# openbook_schematic.net
KiCad netlist of a schematic drawn in EAGLE
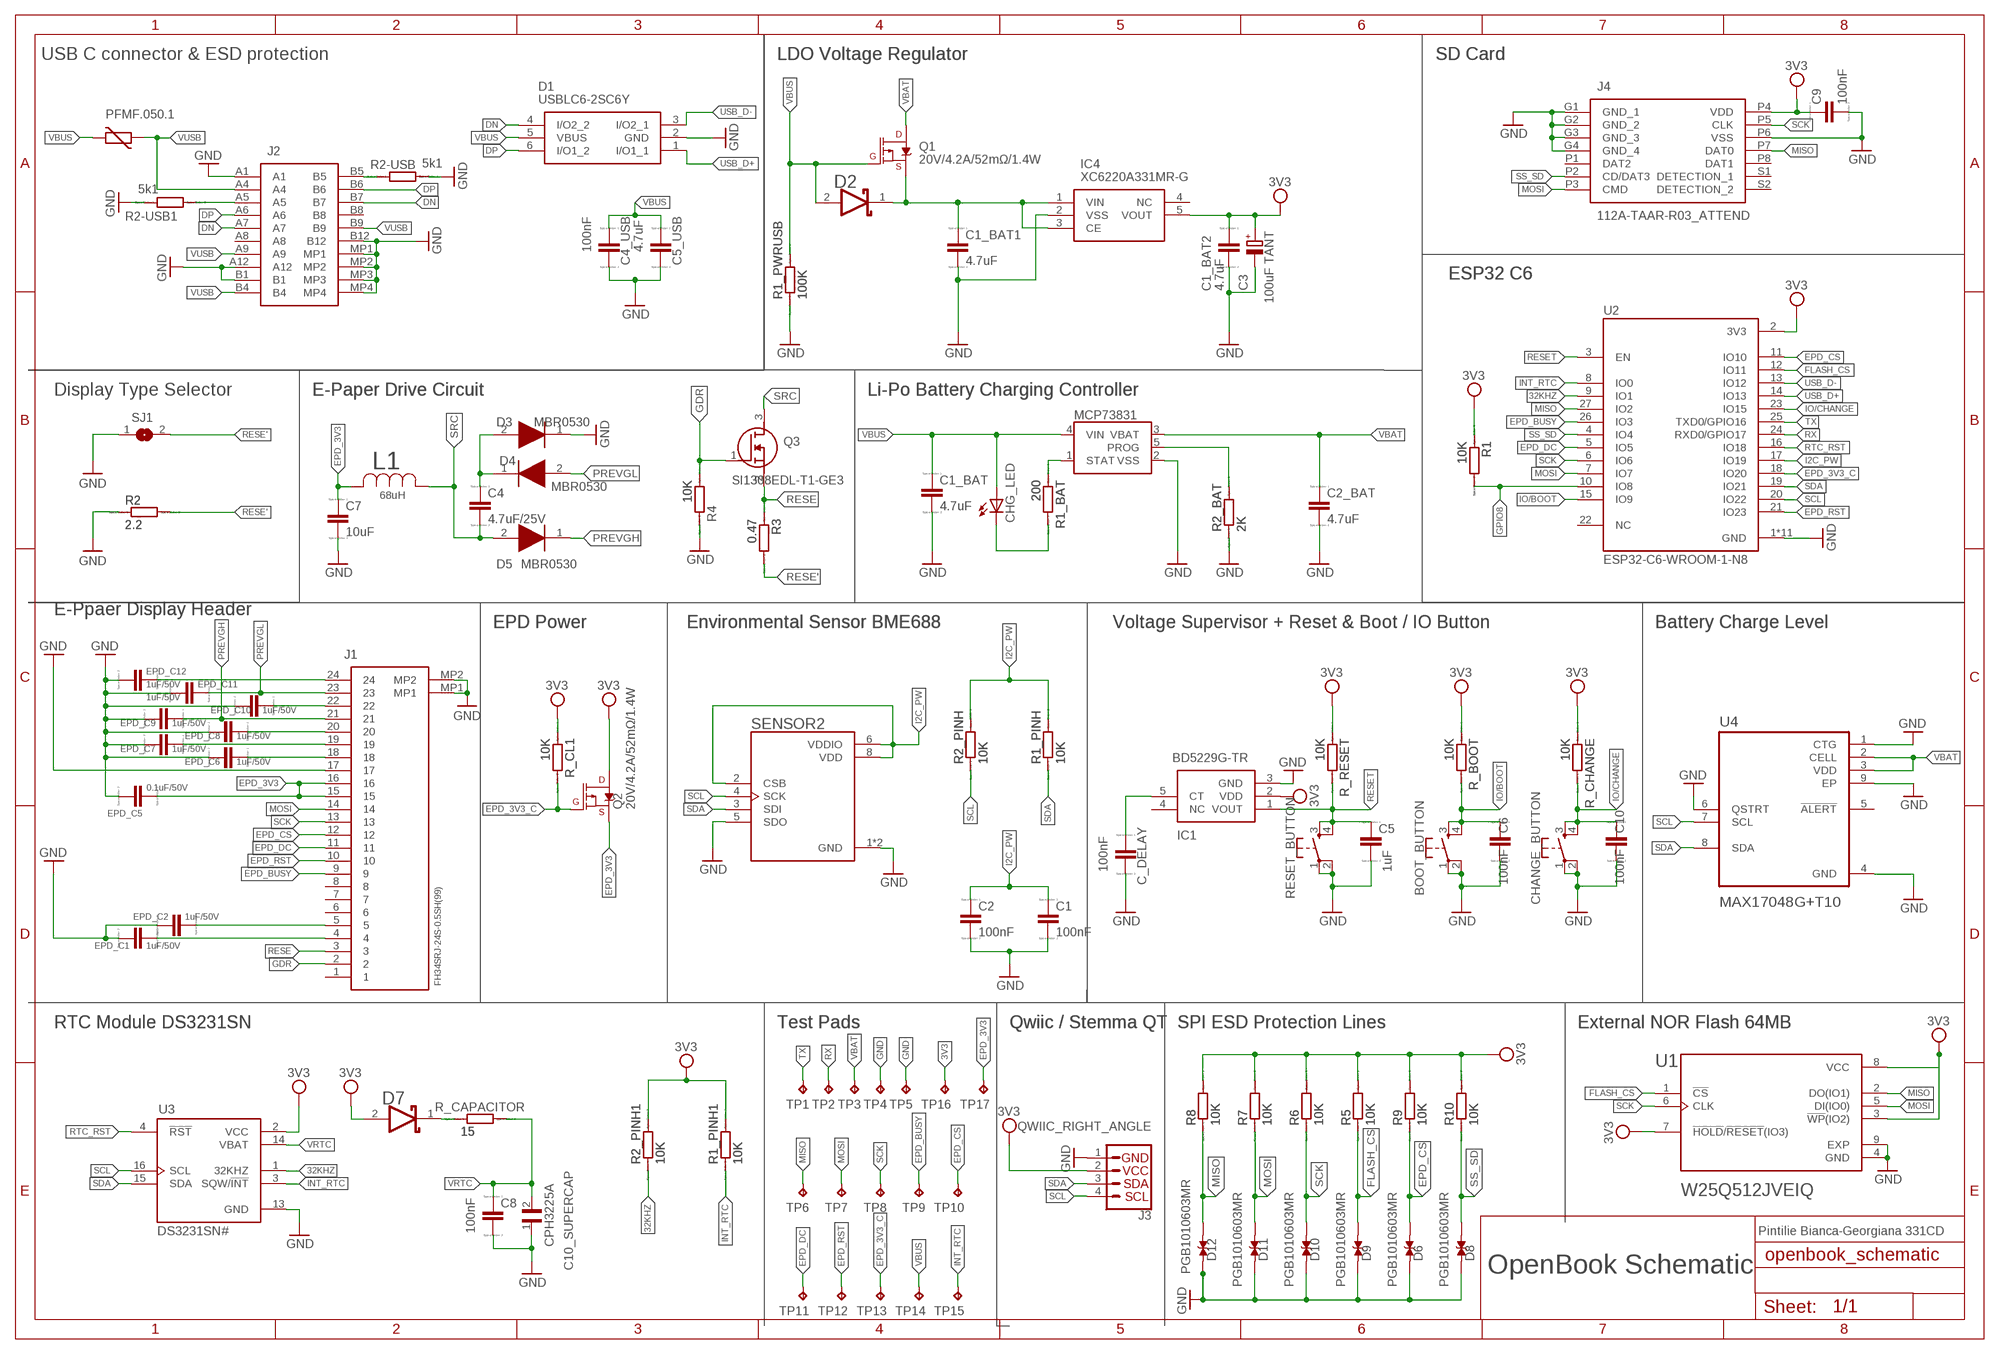
[diagram p0: schematic, sheet 1]

(export (version "E")
  (design (tool "Eeschema 10.0.6"))
  (components
    (comp (ref "BOOT_BUTTON")
      (value "BUTTON_CUSYOMV1")
      (footprint "eagle-import:MYBUTTON")
      (libsource (lib "eagle-import") (part "BUTTON_CUSYOMV1"))
    )
    (comp (ref "C1")
      (value "100nF")
      (footprint "eagle-import:EAGLE-LTSPICE_C0402")
      (libsource (lib "eagle-import") (part "EAGLE-LTSPICE_CC0402"))
    )
    (comp (ref "C1_BAT")
      (value "4.7uF")
      (footprint "eagle-import:EAGLE-LTSPICE_C0402")
      (libsource (lib "eagle-import") (part "EAGLE-LTSPICE_CC0402"))
    )
    (comp (ref "C1_BAT1")
      (value "4.7uF")
      (footprint "eagle-import:EAGLE-LTSPICE_C0402")
      (libsource (lib "eagle-import") (part "EAGLE-LTSPICE_CC0402"))
    )
    (comp (ref "C1_BAT2")
      (value "4.7uF")
      (footprint "eagle-import:EAGLE-LTSPICE_C0402")
      (libsource (lib "eagle-import") (part "EAGLE-LTSPICE_CC0402"))
    )
    (comp (ref "C2")
      (value "100nF")
      (footprint "eagle-import:EAGLE-LTSPICE_C0402")
      (libsource (lib "eagle-import") (part "EAGLE-LTSPICE_CC0402"))
    )
    (comp (ref "C2_BAT")
      (value "4.7uF")
      (footprint "eagle-import:EAGLE-LTSPICE_C0402")
      (libsource (lib "eagle-import") (part "EAGLE-LTSPICE_CC0402"))
    )
    (comp (ref "C3")
      (value "100uF TANT")
      (footprint "eagle-import:RCL_CT3528")
      (libsource (lib "eagle-import") (part "RCL_CPOL-EUCT3528"))
    )
    (comp (ref "C4")
      (value "4.7uF/25V")
      (footprint "eagle-import:EAGLE-LTSPICE_C0402")
      (libsource (lib "eagle-import") (part "EAGLE-LTSPICE_CC0402"))
    )
    (comp (ref "C4_USB")
      (value "100nF")
      (footprint "eagle-import:EAGLE-LTSPICE_C0402")
      (libsource (lib "eagle-import") (part "EAGLE-LTSPICE_CC0402"))
    )
    (comp (ref "C5")
      (value "1uF")
      (footprint "eagle-import:EAGLE-LTSPICE_C0402")
      (libsource (lib "eagle-import") (part "EAGLE-LTSPICE_CC0402"))
    )
    (comp (ref "C5_USB")
      (value "4.7uF")
      (footprint "eagle-import:EAGLE-LTSPICE_C0402")
      (libsource (lib "eagle-import") (part "EAGLE-LTSPICE_CC0402"))
    )
    (comp (ref "C6")
      (value "100nF")
      (footprint "eagle-import:EAGLE-LTSPICE_C0402")
      (libsource (lib "eagle-import") (part "EAGLE-LTSPICE_CC0402"))
    )
    (comp (ref "C7")
      (value "10uF")
      (footprint "eagle-import:EAGLE-LTSPICE_C0402")
      (libsource (lib "eagle-import") (part "EAGLE-LTSPICE_CC0402"))
    )
    (comp (ref "C8")
      (value "100nF")
      (footprint "eagle-import:EAGLE-LTSPICE_C0402")
      (libsource (lib "eagle-import") (part "EAGLE-LTSPICE_CC0402"))
    )
    (comp (ref "C9")
      (value "100nF")
      (footprint "eagle-import:EAGLE-LTSPICE_C0402")
      (libsource (lib "eagle-import") (part "EAGLE-LTSPICE_CC0402"))
    )
    (comp (ref "C10")
      (value "100nF")
      (footprint "eagle-import:EAGLE-LTSPICE_C0402")
      (libsource (lib "eagle-import") (part "EAGLE-LTSPICE_CC0402"))
    )
    (comp (ref "C10_SUPERCAP")
      (value "CPH3225A")
      (footprint "eagle-import:CAPCP3225X100N")
      (fields (field (name "MF") "Seiko Instruments"))
      (libsource (lib "eagle-import") (part "CPH3225A"))
    )
    (comp (ref "CHANGE_BUTTON")
      (value "BUTTON_CUSYOMV1")
      (footprint "eagle-import:MYBUTTON")
      (libsource (lib "eagle-import") (part "BUTTON_CUSYOMV1"))
    )
    (comp (ref "CHG_LED")
      (value "ADAFRUIT_LEDCHIP-LED0603")
      (footprint "eagle-import:ADAFRUIT_CHIP-LED0603")
      (libsource (lib "eagle-import") (part "ADAFRUIT_LEDCHIP-LED0603"))
    )
    (comp (ref "C_DELAY")
      (value "100nF")
      (footprint "eagle-import:EAGLE-LTSPICE_C0402")
      (libsource (lib "eagle-import") (part "EAGLE-LTSPICE_CC0402"))
    )
    (comp (ref "D1")
      (value "USBLC6-2SC6Y")
      (footprint "eagle-import:SOT95P280X145-6N")
      (fields (field (name "MF") "STMicroelectronics"))
      (libsource (lib "eagle-import") (part "USBLC6-2SC6Y"))
    )
    (comp (ref "D2")
      (value "ESP32_WROVER_AVX---SD0805S020S1R0_AVX_SD0805S020S1R0_0_0AVX_SD0805S020S1R0_0_0")
      (footprint "eagle-import:ESP32_WROVER_AVX---SD0805S020S1R0_AVX_SD0805S020S1R0_0")
      (fields
        (field (name "DIGIKEY_PART_NUMBER") "478-7800-1-ND")
        (field (name "MF") "AVX")
        (field (name "MOUSER_PART_NUMBER") "581-SD0805S020S1R0")
      )
      (libsource (lib "eagle-import") (part "ESP32_WROVER_AVX---SD0805S020S1R0_AVX_SD0805S020S1R0_0_0AVX_SD0805S020S1R0_0_0"))
    )
    (comp (ref "D3")
      (value "MBR0530")
      (footprint "eagle-import:SOD3716X135N")
      (fields (field (name "MF") "ON Semiconductor"))
      (libsource (lib "eagle-import") (part "MBR0530"))
    )
    (comp (ref "D4")
      (value "MBR0530")
      (footprint "eagle-import:SOD3716X135N")
      (fields (field (name "MF") "ON Semiconductor"))
      (libsource (lib "eagle-import") (part "MBR0530"))
    )
    (comp (ref "D5")
      (value "MBR0530")
      (footprint "eagle-import:SOD3716X135N")
      (fields (field (name "MF") "ON Semiconductor"))
      (libsource (lib "eagle-import") (part "MBR0530"))
    )
    (comp (ref "D6")
      (value "PGB1010603MR")
      (footprint "eagle-import:DIOC1608X36N")
      (fields (field (name "MF") "Littelfuse Inc."))
      (libsource (lib "eagle-import") (part "PGB1010603MR"))
    )
    (comp (ref "D7")
      (value "ESP32_WROVER_AVX---SD0805S020S1R0_AVX_SD0805S020S1R0_0_0AVX_SD0805S020S1R0_0_0")
      (footprint "eagle-import:ESP32_WROVER_AVX---SD0805S020S1R0_AVX_SD0805S020S1R0_0")
      (fields
        (field (name "DIGIKEY_PART_NUMBER") "478-7800-1-ND")
        (field (name "MF") "AVX")
        (field (name "MOUSER_PART_NUMBER") "581-SD0805S020S1R0")
      )
      (libsource (lib "eagle-import") (part "ESP32_WROVER_AVX---SD0805S020S1R0_AVX_SD0805S020S1R0_0_0AVX_SD0805S020S1R0_0_0"))
    )
    (comp (ref "D8")
      (value "PGB1010603MR")
      (footprint "eagle-import:DIOC1608X36N")
      (fields (field (name "MF") "Littelfuse Inc."))
      (libsource (lib "eagle-import") (part "PGB1010603MR"))
    )
    (comp (ref "D9")
      (value "PGB1010603MR")
      (footprint "eagle-import:DIOC1608X36N")
      (fields (field (name "MF") "Littelfuse Inc."))
      (libsource (lib "eagle-import") (part "PGB1010603MR"))
    )
    (comp (ref "D10")
      (value "PGB1010603MR")
      (footprint "eagle-import:DIOC1608X36N")
      (fields (field (name "MF") "Littelfuse Inc."))
      (libsource (lib "eagle-import") (part "PGB1010603MR"))
    )
    (comp (ref "D11")
      (value "PGB1010603MR")
      (footprint "eagle-import:DIOC1608X36N")
      (fields (field (name "MF") "Littelfuse Inc."))
      (libsource (lib "eagle-import") (part "PGB1010603MR"))
    )
    (comp (ref "D12")
      (value "PGB1010603MR")
      (footprint "eagle-import:DIOC1608X36N")
      (fields (field (name "MF") "Littelfuse Inc."))
      (libsource (lib "eagle-import") (part "PGB1010603MR"))
    )
    (comp (ref "EPD_C1")
      (value "1uF/50V")
      (footprint "eagle-import:ESP32_WROVER_EAGLE-LTSPICE_C0402")
      (libsource (lib "eagle-import") (part "ESP32_WROVER_EAGLE-LTSPICE_CC0402"))
    )
    (comp (ref "EPD_C2")
      (value "1uF/50V")
      (footprint "eagle-import:ESP32_WROVER_EAGLE-LTSPICE_C0402")
      (libsource (lib "eagle-import") (part "ESP32_WROVER_EAGLE-LTSPICE_CC0402"))
    )
    (comp (ref "EPD_C5")
      (value "0.1uF/50V")
      (footprint "eagle-import:ESP32_WROVER_EAGLE-LTSPICE_C0402")
      (libsource (lib "eagle-import") (part "ESP32_WROVER_EAGLE-LTSPICE_CC0402"))
    )
    (comp (ref "EPD_C6")
      (value "1uF/50V")
      (footprint "eagle-import:ESP32_WROVER_EAGLE-LTSPICE_C0402")
      (libsource (lib "eagle-import") (part "ESP32_WROVER_EAGLE-LTSPICE_CC0402"))
    )
    (comp (ref "EPD_C7")
      (value "1uF/50V")
      (footprint "eagle-import:ESP32_WROVER_EAGLE-LTSPICE_C0402")
      (libsource (lib "eagle-import") (part "ESP32_WROVER_EAGLE-LTSPICE_CC0402"))
    )
    (comp (ref "EPD_C8")
      (value "1uF/50V")
      (footprint "eagle-import:ESP32_WROVER_EAGLE-LTSPICE_C0402")
      (libsource (lib "eagle-import") (part "ESP32_WROVER_EAGLE-LTSPICE_CC0402"))
    )
    (comp (ref "EPD_C9")
      (value "1uF/50V")
      (footprint "eagle-import:ESP32_WROVER_EAGLE-LTSPICE_C0402")
      (libsource (lib "eagle-import") (part "ESP32_WROVER_EAGLE-LTSPICE_CC0402"))
    )
    (comp (ref "EPD_C10")
      (value "1uF/50V")
      (footprint "eagle-import:ESP32_WROVER_EAGLE-LTSPICE_C0402")
      (fields (field (name "SPICEPREFIX") "EPD_C10"))
      (libsource (lib "eagle-import") (part "ESP32_WROVER_EAGLE-LTSPICE_CC0402"))
    )
    (comp (ref "EPD_C11")
      (value "1uF/50V")
      (footprint "eagle-import:ESP32_WROVER_EAGLE-LTSPICE_C0402")
      (libsource (lib "eagle-import") (part "ESP32_WROVER_EAGLE-LTSPICE_CC0402"))
    )
    (comp (ref "EPD_C12")
      (value "1uF/50V")
      (footprint "eagle-import:ESP32_WROVER_EAGLE-LTSPICE_C0402")
      (libsource (lib "eagle-import") (part "ESP32_WROVER_EAGLE-LTSPICE_CC0402"))
    )
    (comp (ref "IC1")
      (value "BD5229G-TR")
      (footprint "eagle-import:SOT95P280X125-5N")
      (fields (field (name "MOUSER_PART_NUMBER") "755-BD5229G-TR"))
      (libsource (lib "eagle-import") (part "BD5229G-TR"))
    )
    (comp (ref "IC4")
      (value "XC6220A331MR-G")
      (footprint "eagle-import:SOT95P280X120-5N")
      (fields (field (name "MOUSER_PART_NUMBER") "865-XC6220A331MR-G"))
      (libsource (lib "eagle-import") (part "XC6220A331MR-G"))
    )
    (comp (ref "J1")
      (value "FH34SRJ-24S-0.5SH_99_")
      (footprint "eagle-import:FH34SRJ24S05SH99")
      (fields
        (field (name "MANUFACTURER_PART_NUMBER") "FH34SRJ-24S-0.5SH(99)")
        (field (name "MOUSER_PART_NUMBER") "798-FH34SRJ24S05SH99")
      )
      (libsource (lib "eagle-import") (part "FH34SRJ-24S-0.5SH_99_"))
    )
    (comp (ref "J2")
      (value "SAMACSYS_PARTS_USB4110-GF-A")
      (footprint "eagle-import:SAMACSYS_PARTS_USB4110GFA")
      (fields
        (field (name "MANUFACTURER_PART_NUMBER") "USB4110-GF-A")
        (field (name "MOUSER_PART_NUMBER") "640-USB4110-GF-A")
      )
      (libsource (lib "eagle-import") (part "SAMACSYS_PARTS_USB4110-GF-A"))
    )
    (comp (ref "J3")
      (value "QWIIC_RIGHT_ANGLE")
      (footprint "eagle-import:JST04_1MM_RA")
      (libsource (lib "eagle-import") (part "QWIIC_CONNECTORJS-1MM"))
    )
    (comp (ref "J4")
      (value "112A-TAAR-R03_ATTEND")
      (footprint "eagle-import:112ATAARR03ATTEND")
      (fields (field (name "MANUFACTURER_PART_NUMBER") "112A-TAAR-R03 ATTEND"))
      (libsource (lib "eagle-import") (part "112A-TAAR-R03_ATTEND"))
    )
    (comp (ref "L1")
      (value "68uH")
      (footprint "eagle-import:IND_4828-WE-TPC_WRE")
      (fields
        (field (name "MANUFACTURER_PART_NUMBER") "744043680")
        (field (name "COPYRIGHT") "Copyright (C) 2024 Ultra Librarian. All rights reserved.")
      )
      (libsource (lib "eagle-import") (part "744043680IND_4828-WE-TPC_WRE"))
    )
    (comp (ref "MCP73831")
      (value "ESP32_WROVER_SPARKFUN-IC-POWER_MCP73831")
      (footprint "eagle-import:ESP32_WROVER_SPARKFUN-IC-POWER_SOT23-5")
      (libsource (lib "eagle-import") (part "ESP32_WROVER_SPARKFUN-IC-POWER_MCP73831"))
    )
    (comp (ref "PFMF.050.1")
      (value "ESP32C6_VARISTORCN1812")
      (footprint "eagle-import:ESP32C6_VARISTOR_CT_CN1812")
      (libsource (lib "eagle-import") (part "ESP32C6_VARISTORCN1812"))
    )
    (comp (ref "Q1")
      (value "20V/4.2A/52mΩ/1.4W")
      (footprint "eagle-import:ESP32_WROVER_SPARKFUN-DISCRETESEMI_SOT23-3")
      (libsource (lib "eagle-import") (part "ESP32_WROVER_SPARKFUN-DISCRETESEMI_MOSFET_PCH-DMG2305UX-7"))
    )
    (comp (ref "Q2")
      (value "20V/4.2A/52mΩ/1.4W")
      (footprint "eagle-import:ESP32_WROVER_SPARKFUN-DISCRETESEMI_SOT23-3")
      (libsource (lib "eagle-import") (part "ESP32_WROVER_SPARKFUN-DISCRETESEMI_MOSFET_PCH-DMG2305UX-7"))
    )
    (comp (ref "Q3")
      (value "SI1308EDL-T1-GE3")
      (footprint "eagle-import:SOT65P210X110-3N")
      (fields (field (name "MF") "Vishay Siliconix"))
      (libsource (lib "eagle-import") (part "SI1308EDL-T1-GE3"))
    )
    (comp (ref "R1")
      (value "10K")
      (footprint "eagle-import:ESP32_WROVER_EAGLE-LTSPICE_R0402")
      (libsource (lib "eagle-import") (part "ESP32_WROVER_EAGLE-LTSPICE_RR0402"))
    )
    (comp (ref "R1_BAT")
      (value "200")
      (footprint "eagle-import:ESP32_WROVER_EAGLE-LTSPICE_R0402")
      (libsource (lib "eagle-import") (part "ESP32_WROVER_EAGLE-LTSPICE_RR0402"))
    )
    (comp (ref "R1_PINH")
      (value "10K")
      (footprint "eagle-import:ESP32_WROVER_EAGLE-LTSPICE_R0402")
      (libsource (lib "eagle-import") (part "ESP32_WROVER_EAGLE-LTSPICE_RR0402"))
    )
    (comp (ref "R1_PINH1")
      (value "10K")
      (footprint "eagle-import:ESP32_WROVER_EAGLE-LTSPICE_R0402")
      (libsource (lib "eagle-import") (part "ESP32_WROVER_EAGLE-LTSPICE_RR0402"))
    )
    (comp (ref "R1_PWRUSB")
      (value "100K")
      (footprint "eagle-import:ESP32_WROVER_EAGLE-LTSPICE_R0402")
      (libsource (lib "eagle-import") (part "ESP32_WROVER_EAGLE-LTSPICE_RR0402"))
    )
    (comp (ref "R2")
      (value "2.2")
      (footprint "eagle-import:ESP32_WROVER_EAGLE-LTSPICE_R0402")
      (libsource (lib "eagle-import") (part "ESP32_WROVER_EAGLE-LTSPICE_RR0402"))
    )
    (comp (ref "R2-USB")
      (value "5k1")
      (footprint "eagle-import:ESP32_WROVER_EAGLE-LTSPICE_R0402")
      (libsource (lib "eagle-import") (part "ESP32_WROVER_EAGLE-LTSPICE_RR0402"))
    )
    (comp (ref "R2-USB1")
      (value "5k1")
      (footprint "eagle-import:ESP32_WROVER_EAGLE-LTSPICE_R0402")
      (libsource (lib "eagle-import") (part "ESP32_WROVER_EAGLE-LTSPICE_RR0402"))
    )
    (comp (ref "R2_BAT")
      (value "2K")
      (footprint "eagle-import:ESP32_WROVER_EAGLE-LTSPICE_R0402")
      (libsource (lib "eagle-import") (part "ESP32_WROVER_EAGLE-LTSPICE_RR0402"))
    )
    (comp (ref "R2_PINH")
      (value "10K")
      (footprint "eagle-import:ESP32_WROVER_EAGLE-LTSPICE_R0402")
      (libsource (lib "eagle-import") (part "ESP32_WROVER_EAGLE-LTSPICE_RR0402"))
    )
    (comp (ref "R2_PINH1")
      (value "10K")
      (footprint "eagle-import:ESP32_WROVER_EAGLE-LTSPICE_R0402")
      (libsource (lib "eagle-import") (part "ESP32_WROVER_EAGLE-LTSPICE_RR0402"))
    )
    (comp (ref "R3")
      (value "0.47")
      (footprint "eagle-import:ESP32_WROVER_EAGLE-LTSPICE_R0402")
      (libsource (lib "eagle-import") (part "ESP32_WROVER_EAGLE-LTSPICE_RR0402"))
    )
    (comp (ref "R4")
      (value "10K")
      (footprint "eagle-import:ESP32_WROVER_EAGLE-LTSPICE_R0402")
      (libsource (lib "eagle-import") (part "ESP32_WROVER_EAGLE-LTSPICE_RR0402"))
    )
    (comp (ref "R5")
      (value "10K")
      (footprint "eagle-import:ESP32_WROVER_EAGLE-LTSPICE_R0402")
      (libsource (lib "eagle-import") (part "ESP32_WROVER_EAGLE-LTSPICE_RR0402"))
    )
    (comp (ref "R6")
      (value "10K")
      (footprint "eagle-import:ESP32_WROVER_EAGLE-LTSPICE_R0402")
      (libsource (lib "eagle-import") (part "ESP32_WROVER_EAGLE-LTSPICE_RR0402"))
    )
    (comp (ref "R7")
      (value "10K")
      (footprint "eagle-import:ESP32_WROVER_EAGLE-LTSPICE_R0402")
      (libsource (lib "eagle-import") (part "ESP32_WROVER_EAGLE-LTSPICE_RR0402"))
    )
    (comp (ref "R8")
      (value "10K")
      (footprint "eagle-import:ESP32_WROVER_EAGLE-LTSPICE_R0402")
      (libsource (lib "eagle-import") (part "ESP32_WROVER_EAGLE-LTSPICE_RR0402"))
    )
    (comp (ref "R9")
      (value "10K")
      (footprint "eagle-import:ESP32_WROVER_EAGLE-LTSPICE_R0402")
      (libsource (lib "eagle-import") (part "ESP32_WROVER_EAGLE-LTSPICE_RR0402"))
    )
    (comp (ref "R10")
      (value "10K")
      (footprint "eagle-import:ESP32_WROVER_EAGLE-LTSPICE_R0402")
      (libsource (lib "eagle-import") (part "ESP32_WROVER_EAGLE-LTSPICE_RR0402"))
    )
    (comp (ref "RESET_BUTTON")
      (value "BUTTON_CUSYOMV1")
      (footprint "eagle-import:MYBUTTON")
      (libsource (lib "eagle-import") (part "BUTTON_CUSYOMV1"))
    )
    (comp (ref "R_BOOT")
      (value "10K")
      (footprint "eagle-import:ESP32_WROVER_EAGLE-LTSPICE_R0402")
      (libsource (lib "eagle-import") (part "ESP32_WROVER_EAGLE-LTSPICE_RR0402"))
    )
    (comp (ref "R_CAPACITOR")
      (value "15")
      (footprint "eagle-import:ESP32_WROVER_EAGLE-LTSPICE_R0402")
      (libsource (lib "eagle-import") (part "ESP32_WROVER_EAGLE-LTSPICE_RR0402"))
    )
    (comp (ref "R_CHANGE")
      (value "10K")
      (footprint "eagle-import:ESP32_WROVER_EAGLE-LTSPICE_R0402")
      (libsource (lib "eagle-import") (part "ESP32_WROVER_EAGLE-LTSPICE_RR0402"))
    )
    (comp (ref "R_CL1")
      (value "10K")
      (footprint "eagle-import:ESP32_WROVER_EAGLE-LTSPICE_R0402")
      (libsource (lib "eagle-import") (part "ESP32_WROVER_EAGLE-LTSPICE_RR0402"))
    )
    (comp (ref "R_RESET")
      (value "10K")
      (footprint "eagle-import:ESP32_WROVER_EAGLE-LTSPICE_R0402")
      (libsource (lib "eagle-import") (part "ESP32_WROVER_EAGLE-LTSPICE_RR0402"))
    )
    (comp (ref "SENSOR2")
      (value "ESP32_WROVER_BME680_BME680")
      (footprint "eagle-import:ESP32_WROVER_BME680_PSON80P300X300X100-8N")
      (fields (field (name "MF") "Bosch Sensortec") (field (name "MP") "BME680"))
      (libsource (lib "eagle-import") (part "ESP32_WROVER_BME680_BME680"))
    )
    (comp (ref "SJ1") (value "SJ") (footprint "eagle-import:SJ") (libsource (lib "eagle-import") (part "SJ")))
    (comp (ref "TP1")
      (value "TPTP20R")
      (footprint "eagle-import:TP20R")
      (libsource (lib "eagle-import") (part "TPTP20R"))
    )
    (comp (ref "TP2")
      (value "TPTP20R")
      (footprint "eagle-import:TP20R")
      (libsource (lib "eagle-import") (part "TPTP20R"))
    )
    (comp (ref "TP3")
      (value "TPTP20R")
      (footprint "eagle-import:TP20R")
      (libsource (lib "eagle-import") (part "TPTP20R"))
    )
    (comp (ref "TP4")
      (value "TPTP20R")
      (footprint "eagle-import:TP20R")
      (libsource (lib "eagle-import") (part "TPTP20R"))
    )
    (comp (ref "TP5")
      (value "TPTP20R")
      (footprint "eagle-import:TP20R")
      (libsource (lib "eagle-import") (part "TPTP20R"))
    )
    (comp (ref "TP6")
      (value "TPTP20R")
      (footprint "eagle-import:TP20R")
      (libsource (lib "eagle-import") (part "TPTP20R"))
    )
    (comp (ref "TP7")
      (value "TPTP20R")
      (footprint "eagle-import:TP20R")
      (libsource (lib "eagle-import") (part "TPTP20R"))
    )
    (comp (ref "TP8")
      (value "TPTP20R")
      (footprint "eagle-import:TP20R")
      (libsource (lib "eagle-import") (part "TPTP20R"))
    )
    (comp (ref "TP9")
      (value "TPTP20R")
      (footprint "eagle-import:TP20R")
      (libsource (lib "eagle-import") (part "TPTP20R"))
    )
    (comp (ref "TP10")
      (value "TPTP20R")
      (footprint "eagle-import:TP20R")
      (libsource (lib "eagle-import") (part "TPTP20R"))
    )
    (comp (ref "TP11")
      (value "TPTP20R")
      (footprint "eagle-import:TP20R")
      (libsource (lib "eagle-import") (part "TPTP20R"))
    )
    (comp (ref "TP12")
      (value "TPTP20R")
      (footprint "eagle-import:TP20R")
      (libsource (lib "eagle-import") (part "TPTP20R"))
    )
    (comp (ref "TP13")
      (value "TPTP20R")
      (footprint "eagle-import:TP20R")
      (libsource (lib "eagle-import") (part "TPTP20R"))
    )
    (comp (ref "TP14")
      (value "TPTP20R")
      (footprint "eagle-import:TP20R")
      (libsource (lib "eagle-import") (part "TPTP20R"))
    )
    (comp (ref "TP15")
      (value "TPTP20R")
      (footprint "eagle-import:TP20R")
      (libsource (lib "eagle-import") (part "TPTP20R"))
    )
    (comp (ref "TP16")
      (value "TPTP20R")
      (footprint "eagle-import:TP20R")
      (libsource (lib "eagle-import") (part "TPTP20R"))
    )
    (comp (ref "TP17")
      (value "TPTP20R")
      (footprint "eagle-import:TP20R")
      (libsource (lib "eagle-import") (part "TPTP20R"))
    )
    (comp (ref "U1")
      (value "W25Q512JVEIQ")
      (footprint "eagle-import:SON127P600X800X80-9N")
      (fields (field (name "MF") "Winbond Electronics"))
      (libsource (lib "eagle-import") (part "W25Q512JVEIQ"))
    )
    (comp (ref "U2")
      (value "ESP32-C6-WROOM-1-N8")
      (footprint "eagle-import:XCVR_ESP32-C6-WROOM-1-N8")
      (fields (field (name "MF") "Espressif Systems"))
      (libsource (lib "eagle-import") (part "ESP32-C6-WROOM-1-N8"))
    )
    (comp (ref "U3")
      (value "DS3231SN#")
      (footprint "eagle-import:SOIC127P1032X265-16N")
      (fields (field (name "MF") "Analog Devices"))
      (libsource (lib "eagle-import") (part "DS3231SN#"))
    )
    (comp (ref "U4")
      (value "MAX17048G+T10")
      (footprint "eagle-import:SON50P200X200X80-9N")
      (fields (field (name "MF") "Analog Devices"))
      (libsource (lib "eagle-import") (part "MAX17048G+T10"))
    )
  )
  (nets
    (net (code "1") (name "3V3") (class "Default")
      (node (ref "C1_BAT2") (pin "1") (pinfunction "1_1") (pintype "passive"))
      (node (ref "C3") (pin "+") (pinfunction "+_+") (pintype "passive"))
      (node (ref "C9") (pin "1") (pinfunction "1_1") (pintype "passive"))
      (node (ref "D7") (pin "2") (pinfunction "ANODE_2") (pintype "bidirectional"))
      (node (ref "IC1") (pin "2") (pinfunction "VDD_2") (pintype "bidirectional"))
      (node (ref "IC4") (pin "5") (pinfunction "VOUT_5") (pintype "bidirectional"))
      (node (ref "J3") (pin "2") (pinfunction "2_2") (pintype "power_in"))
      (node (ref "J4") (pin "P4") (pinfunction "VDD_P4") (pintype "bidirectional"))
      (node (ref "Q2") (pin "3") (pinfunction "D_3") (pintype "bidirectional"))
      (node (ref "R1") (pin "1") (pinfunction "1_1") (pintype "passive"))
      (node (ref "R10") (pin "2") (pinfunction "2_2") (pintype "passive"))
      (node (ref "R1_PINH1") (pin "2") (pinfunction "2_2") (pintype "passive"))
      (node (ref "R2_PINH1") (pin "2") (pinfunction "2_2") (pintype "passive"))
      (node (ref "R5") (pin "2") (pinfunction "2_2") (pintype "passive"))
      (node (ref "R6") (pin "2") (pinfunction "2_2") (pintype "passive"))
      (node (ref "R7") (pin "2") (pinfunction "2_2") (pintype "passive"))
      (node (ref "R8") (pin "2") (pinfunction "2_2") (pintype "passive"))
      (node (ref "R9") (pin "2") (pinfunction "2_2") (pintype "passive"))
      (node (ref "R_BOOT") (pin "1") (pinfunction "1_1") (pintype "passive"))
      (node (ref "R_CHANGE") (pin "1") (pinfunction "1_1") (pintype "passive"))
      (node (ref "R_CL1") (pin "1") (pinfunction "1_1") (pintype "passive"))
      (node (ref "R_RESET") (pin "1") (pinfunction "1_1") (pintype "passive"))
      (node (ref "TP16") (pin "TP") (pinfunction "TP_TP") (pintype "input"))
      (node (ref "U1") (pin "3") (pinfunction "~{WP}(IO2)_3") (pintype "bidirectional"))
      (node (ref "U1") (pin "7") (pinfunction "~{HOLD}/~{RESET}(IO3)_7") (pintype "bidirectional"))
      (node (ref "U1") (pin "8") (pinfunction "VCC_8") (pintype "power_in"))
      (node (ref "U2") (pin "2") (pinfunction "3V3_2") (pintype "power_in"))
      (node (ref "U3") (pin "2") (pinfunction "VCC_2") (pintype "power_in"))
    )
    (net (code "2") (name "32KHZ") (class "Default")
      (node (ref "R2_PINH1") (pin "1") (pinfunction "1_1") (pintype "passive"))
      (node (ref "U2") (pin "9") (pinfunction "IO1_9") (pintype "bidirectional"))
      (node (ref "U3") (pin "1") (pinfunction "32KHZ_1") (pintype "output"))
    )
    (net (code "3") (name "DN") (class "Default")
      (node (ref "D1") (pin "4") (pinfunction "I/O2_2_4") (pintype "bidirectional"))
      (node (ref "J2") (pin "A7") (pinfunction "A7_A7") (pintype "bidirectional"))
      (node (ref "J2") (pin "B7") (pinfunction "B7_B7") (pintype "bidirectional"))
    )
    (net (code "4") (name "DP") (class "Default")
      (node (ref "D1") (pin "6") (pinfunction "I/O1_2_6") (pintype "bidirectional"))
      (node (ref "J2") (pin "A6") (pinfunction "A6_A6") (pintype "bidirectional"))
      (node (ref "J2") (pin "B6") (pinfunction "B6_B6") (pintype "bidirectional"))
    )
    (net (code "5") (name "EPD_3V3") (class "Default")
      (node (ref "C7") (pin "1") (pinfunction "1_1") (pintype "passive"))
      (node (ref "EPD_C5") (pin "1") (pinfunction "1_1") (pintype "passive"))
      (node (ref "J1") (pin "15") (pinfunction "15_15") (pintype "bidirectional"))
      (node (ref "J1") (pin "16") (pinfunction "16_16") (pintype "bidirectional"))
      (node (ref "L1") (pin "2") (pinfunction "2_2") (pintype "passive"))
      (node (ref "Q2") (pin "2") (pinfunction "S_2") (pintype "bidirectional"))
      (node (ref "TP17") (pin "TP") (pinfunction "TP_TP") (pintype "input"))
    )
    (net (code "6") (name "EPD_3V3_C") (class "Default")
      (node (ref "Q2") (pin "1") (pinfunction "G_1") (pintype "bidirectional"))
      (node (ref "R_CL1") (pin "2") (pinfunction "2_2") (pintype "passive"))
      (node (ref "TP13") (pin "TP") (pinfunction "TP_TP") (pintype "input"))
      (node (ref "U2") (pin "18") (pinfunction "IO20_18") (pintype "bidirectional"))
    )
    (net (code "7") (name "EPD_BUSY") (class "Default")
      (node (ref "J1") (pin "9") (pinfunction "9_9") (pintype "bidirectional"))
      (node (ref "TP9") (pin "TP") (pinfunction "TP_TP") (pintype "input"))
      (node (ref "U2") (pin "26") (pinfunction "IO3_26") (pintype "bidirectional"))
    )
    (net (code "8") (name "EPD_CS") (class "Default")
      (node (ref "D6") (pin "2") (pinfunction "2_2") (pintype "passive"))
      (node (ref "J1") (pin "12") (pinfunction "12_12") (pintype "bidirectional"))
      (node (ref "R9") (pin "1") (pinfunction "1_1") (pintype "passive"))
      (node (ref "TP10") (pin "TP") (pinfunction "TP_TP") (pintype "input"))
      (node (ref "U2") (pin "11") (pinfunction "IO10_11") (pintype "bidirectional"))
    )
    (net (code "9") (name "EPD_DC") (class "Default")
      (node (ref "J1") (pin "11") (pinfunction "11_11") (pintype "bidirectional"))
      (node (ref "TP11") (pin "TP") (pinfunction "TP_TP") (pintype "input"))
      (node (ref "U2") (pin "5") (pinfunction "IO5_5") (pintype "bidirectional"))
    )
    (net (code "10") (name "EPD_RST") (class "Default")
      (node (ref "J1") (pin "10") (pinfunction "10_10") (pintype "bidirectional"))
      (node (ref "TP12") (pin "TP") (pinfunction "TP_TP") (pintype "input"))
      (node (ref "U2") (pin "21") (pinfunction "IO23_21") (pintype "bidirectional"))
    )
    (net (code "11") (name "FLASH_CS") (class "Default")
      (node (ref "D9") (pin "2") (pinfunction "2_2") (pintype "passive"))
      (node (ref "R5") (pin "1") (pinfunction "1_1") (pintype "passive"))
      (node (ref "U1") (pin "1") (pinfunction "~{CS}_1") (pintype "input"))
      (node (ref "U2") (pin "12") (pinfunction "IO11_12") (pintype "bidirectional"))
    )
    (net (code "12") (name "GDR") (class "Default")
      (node (ref "J1") (pin "2") (pinfunction "2_2") (pintype "bidirectional"))
      (node (ref "Q3") (pin "1") (pinfunction "G_1") (pintype "bidirectional"))
      (node (ref "R4") (pin "1") (pinfunction "1_1") (pintype "passive"))
    )
    (net (code "13") (name "GND") (class "Default")
      (node (ref "BOOT_BUTTON") (pin "1") (pinfunction "1_1") (pintype "passive"))
      (node (ref "BOOT_BUTTON") (pin "2") (pinfunction "2_2") (pintype "passive"))
      (node (ref "C1") (pin "2") (pinfunction "2_2") (pintype "passive"))
      (node (ref "C10") (pin "2") (pinfunction "2_2") (pintype "passive"))
      (node (ref "C10_SUPERCAP") (pin "1") (pinfunction "1_1") (pintype "passive"))
      (node (ref "C1_BAT") (pin "2") (pinfunction "2_2") (pintype "passive"))
      (node (ref "C1_BAT1") (pin "2") (pinfunction "2_2") (pintype "passive"))
      (node (ref "C1_BAT2") (pin "2") (pinfunction "2_2") (pintype "passive"))
      (node (ref "C2") (pin "2") (pinfunction "2_2") (pintype "passive"))
      (node (ref "C2_BAT") (pin "2") (pinfunction "2_2") (pintype "passive"))
      (node (ref "C3") (pin "-") (pinfunction "-_-") (pintype "passive"))
      (node (ref "C4_USB") (pin "2") (pinfunction "2_2") (pintype "passive"))
      (node (ref "C5") (pin "2") (pinfunction "2_2") (pintype "passive"))
      (node (ref "C5_USB") (pin "2") (pinfunction "2_2") (pintype "passive"))
      (node (ref "C6") (pin "2") (pinfunction "2_2") (pintype "passive"))
      (node (ref "C7") (pin "2") (pinfunction "2_2") (pintype "passive"))
      (node (ref "C8") (pin "2") (pinfunction "2_2") (pintype "passive"))
      (node (ref "C9") (pin "2") (pinfunction "2_2") (pintype "passive"))
      (node (ref "CHANGE_BUTTON") (pin "1") (pinfunction "1_1") (pintype "passive"))
      (node (ref "CHANGE_BUTTON") (pin "2") (pinfunction "2_2") (pintype "passive"))
      (node (ref "C_DELAY") (pin "2") (pinfunction "2_2") (pintype "passive"))
      (node (ref "D1") (pin "2") (pinfunction "GND_2") (pintype "bidirectional"))
      (node (ref "D10") (pin "1") (pinfunction "1_1") (pintype "passive"))
      (node (ref "D11") (pin "1") (pinfunction "1_1") (pintype "passive"))
      (node (ref "D12") (pin "1") (pinfunction "1_1") (pintype "passive"))
      (node (ref "D3") (pin "1") (pinfunction "K_1") (pintype "bidirectional"))
      (node (ref "D6") (pin "1") (pinfunction "1_1") (pintype "passive"))
      (node (ref "D8") (pin "1") (pinfunction "1_1") (pintype "passive"))
      (node (ref "D9") (pin "1") (pinfunction "1_1") (pintype "passive"))
      (node (ref "EPD_C1") (pin "2") (pinfunction "2_2") (pintype "passive"))
      (node (ref "EPD_C10") (pin "2") (pinfunction "2_2") (pintype "passive"))
      (node (ref "EPD_C11") (pin "2") (pinfunction "2_2") (pintype "passive"))
      (node (ref "EPD_C12") (pin "2") (pinfunction "2_2") (pintype "passive"))
      (node (ref "EPD_C2") (pin "2") (pinfunction "2_2") (pintype "passive"))
      (node (ref "EPD_C5") (pin "2") (pinfunction "2_2") (pintype "passive"))
      (node (ref "EPD_C6") (pin "2") (pinfunction "2_2") (pintype "passive"))
      (node (ref "EPD_C7") (pin "2") (pinfunction "2_2") (pintype "passive"))
      (node (ref "EPD_C8") (pin "2") (pinfunction "2_2") (pintype "passive"))
      (node (ref "EPD_C9") (pin "2") (pinfunction "2_2") (pintype "passive"))
      (node (ref "IC1") (pin "3") (pinfunction "GND_3") (pintype "bidirectional"))
      (node (ref "IC4") (pin "2") (pinfunction "VSS_2") (pintype "bidirectional"))
      (node (ref "J1") (pin "17") (pinfunction "17_17") (pintype "bidirectional"))
      (node (ref "J1") (pin "MP1") (pinfunction "MP1_MP1") (pintype "bidirectional"))
      (node (ref "J1") (pin "MP2") (pinfunction "MP2_MP2") (pintype "bidirectional"))
      (node (ref "J2") (pin "A1") (pinfunction "A1_A1") (pintype "bidirectional"))
      (node (ref "J2") (pin "A12") (pinfunction "A12_A12") (pintype "bidirectional"))
      (node (ref "J2") (pin "B1") (pinfunction "B1_B1") (pintype "bidirectional"))
      (node (ref "J2") (pin "B12") (pinfunction "B12_B12") (pintype "bidirectional"))
      (node (ref "J2") (pin "MP1") (pinfunction "MP1_MP1") (pintype "bidirectional"))
      (node (ref "J2") (pin "MP2") (pinfunction "MP2_MP2") (pintype "bidirectional"))
      (node (ref "J2") (pin "MP3") (pinfunction "MP3_MP3") (pintype "bidirectional"))
      (node (ref "J2") (pin "MP4") (pinfunction "MP4_MP4") (pintype "bidirectional"))
      (node (ref "J3") (pin "1") (pinfunction "1_1") (pintype "power_in"))
      (node (ref "J4") (pin "G1") (pinfunction "GND_1_G1") (pintype "bidirectional"))
      (node (ref "J4") (pin "G2") (pinfunction "GND_2_G2") (pintype "bidirectional"))
      (node (ref "J4") (pin "G3") (pinfunction "GND_3_G3") (pintype "bidirectional"))
      (node (ref "J4") (pin "G4") (pinfunction "GND_4_G4") (pintype "bidirectional"))
      (node (ref "J4") (pin "P6") (pinfunction "VSS_P6") (pintype "bidirectional"))
      (node (ref "MCP73831") (pin "2") (pinfunction "VSS_2") (pintype "power_in"))
      (node (ref "R1_PWRUSB") (pin "1") (pinfunction "1_1") (pintype "passive"))
      (node (ref "R2") (pin "1") (pinfunction "1_1") (pintype "passive"))
      (node (ref "R2-USB") (pin "2") (pinfunction "2_2") (pintype "passive"))
      (node (ref "R2-USB1") (pin "1") (pinfunction "1_1") (pintype "passive"))
      (node (ref "R2_BAT") (pin "1") (pinfunction "1_1") (pintype "passive"))
      (node (ref "R4") (pin "2") (pinfunction "2_2") (pintype "passive"))
      (node (ref "RESET_BUTTON") (pin "1") (pinfunction "1_1") (pintype "passive"))
      (node (ref "RESET_BUTTON") (pin "2") (pinfunction "2_2") (pintype "passive"))
      (node (ref "SENSOR2") (pin "1") (pinfunction "GND_1") (pintype "power_in"))
      (node (ref "SENSOR2") (pin "5") (pinfunction "SDO_5") (pintype "bidirectional"))
      (node (ref "SENSOR2") (pin "7") (pinfunction "GND_7") (pintype "power_in"))
      (node (ref "SJ1") (pin "1") (pinfunction "1_1") (pintype "passive"))
      (node (ref "TP4") (pin "TP") (pinfunction "TP_TP") (pintype "input"))
      (node (ref "TP5") (pin "TP") (pinfunction "TP_TP") (pintype "input"))
      (node (ref "U1") (pin "4") (pinfunction "GND_4") (pintype "power_in"))
      (node (ref "U1") (pin "9") (pinfunction "EXP_9") (pintype "passive"))
      (node (ref "U2") (pin "1") (pinfunction "GND_1") (pintype "power_in"))
      (node (ref "U2") (pin "28") (pinfunction "GND_28") (pintype "power_in"))
      (node (ref "U2") (pin "29_1") (pinfunction "GND_29_1") (pintype "power_in"))
      (node (ref "U2") (pin "29_2") (pinfunction "GND_29_2") (pintype "power_in"))
      (node (ref "U2") (pin "29_3") (pinfunction "GND_29_3") (pintype "power_in"))
      (node (ref "U2") (pin "29_4") (pinfunction "GND_29_4") (pintype "power_in"))
      (node (ref "U2") (pin "29_5") (pinfunction "GND_29_5") (pintype "power_in"))
      (node (ref "U2") (pin "29_6") (pinfunction "GND_29_6") (pintype "power_in"))
      (node (ref "U2") (pin "29_7") (pinfunction "GND_29_7") (pintype "power_in"))
      (node (ref "U2") (pin "29_8") (pinfunction "GND_29_8") (pintype "power_in"))
      (node (ref "U2") (pin "29_9") (pinfunction "GND_29_9") (pintype "power_in"))
      (node (ref "U3") (pin "13") (pinfunction "GND_13") (pintype "power_in"))
      (node (ref "U4") (pin "1") (pinfunction "CTG_1") (pintype "power_in"))
      (node (ref "U4") (pin "4") (pinfunction "GND_4") (pintype "power_in"))
      (node (ref "U4") (pin "6") (pinfunction "QSTRT_6") (pintype "input"))
      (node (ref "U4") (pin "9") (pinfunction "EP_9") (pintype "power_in"))
    )
    (net (code "14") (name "GPIO8") (class "Default")
      (node (ref "R1") (pin "2") (pinfunction "2_2") (pintype "passive"))
      (node (ref "U2") (pin "10") (pinfunction "IO8_10") (pintype "bidirectional"))
    )
    (net (code "15") (name "I2C_PW") (class "Default")
      (node (ref "C1") (pin "1") (pinfunction "1_1") (pintype "passive"))
      (node (ref "C2") (pin "1") (pinfunction "1_1") (pintype "passive"))
      (node (ref "R1_PINH") (pin "2") (pinfunction "2_2") (pintype "passive"))
      (node (ref "R2_PINH") (pin "2") (pinfunction "2_2") (pintype "passive"))
      (node (ref "SENSOR2") (pin "2") (pinfunction "CSB_2") (pintype "input"))
      (node (ref "SENSOR2") (pin "6") (pinfunction "VDDIO_6") (pintype "power_in"))
      (node (ref "SENSOR2") (pin "8") (pinfunction "VDD_8") (pintype "power_in"))
      (node (ref "U2") (pin "17") (pinfunction "IO19_17") (pintype "bidirectional"))
    )
    (net (code "16") (name "INT_RTC") (class "Default")
      (node (ref "R1_PINH1") (pin "1") (pinfunction "1_1") (pintype "passive"))
      (node (ref "TP15") (pin "TP") (pinfunction "TP_TP") (pintype "input"))
      (node (ref "U2") (pin "8") (pinfunction "IO0_8") (pintype "bidirectional"))
      (node (ref "U3") (pin "3") (pinfunction "SQW/~{INT}_3") (pintype "output"))
    )
    (net (code "17") (name "IO{slash}BOOT") (class "Default")
      (node (ref "BOOT_BUTTON") (pin "3") (pinfunction "3_3") (pintype "passive"))
      (node (ref "BOOT_BUTTON") (pin "4") (pinfunction "4_4") (pintype "passive"))
      (node (ref "C6") (pin "1") (pinfunction "1_1") (pintype "passive"))
      (node (ref "R_BOOT") (pin "2") (pinfunction "2_2") (pintype "passive"))
      (node (ref "U2") (pin "15") (pinfunction "IO9_15") (pintype "bidirectional"))
    )
    (net (code "18") (name "IO{slash}CHANGE") (class "Default")
      (node (ref "C10") (pin "1") (pinfunction "1_1") (pintype "passive"))
      (node (ref "CHANGE_BUTTON") (pin "3") (pinfunction "3_3") (pintype "passive"))
      (node (ref "CHANGE_BUTTON") (pin "4") (pinfunction "4_4") (pintype "passive"))
      (node (ref "R_CHANGE") (pin "2") (pinfunction "2_2") (pintype "passive"))
      (node (ref "U2") (pin "23") (pinfunction "IO15_23") (pintype "bidirectional"))
    )
    (net (code "19") (name "MISO") (class "Default")
      (node (ref "D12") (pin "2") (pinfunction "2_2") (pintype "passive"))
      (node (ref "J4") (pin "P7") (pinfunction "DAT0_P7") (pintype "bidirectional"))
      (node (ref "R8") (pin "1") (pinfunction "1_1") (pintype "passive"))
      (node (ref "TP6") (pin "TP") (pinfunction "TP_TP") (pintype "input"))
      (node (ref "U1") (pin "2") (pinfunction "DO(IO1)_2") (pintype "bidirectional"))
      (node (ref "U2") (pin "27") (pinfunction "IO2_27") (pintype "bidirectional"))
    )
    (net (code "20") (name "MOSI") (class "Default")
      (node (ref "D11") (pin "2") (pinfunction "2_2") (pintype "passive"))
      (node (ref "J1") (pin "14") (pinfunction "14_14") (pintype "bidirectional"))
      (node (ref "J4") (pin "P3") (pinfunction "CMD_P3") (pintype "bidirectional"))
      (node (ref "R7") (pin "1") (pinfunction "1_1") (pintype "passive"))
      (node (ref "TP7") (pin "TP") (pinfunction "TP_TP") (pintype "input"))
      (node (ref "U1") (pin "5") (pinfunction "DI(IO0)_5") (pintype "bidirectional"))
      (node (ref "U2") (pin "7") (pinfunction "IO7_7") (pintype "bidirectional"))
    )
    (net (code "21") (name "Net-(CHG_LED-PadC)") (class "Default")
      (node (ref "CHG_LED") (pin "C") (pinfunction "C_C") (pintype "passive"))
      (node (ref "R1_BAT") (pin "2") (pinfunction "2_2") (pintype "passive"))
    )
    (net (code "22") (name "Net-(D2-CATHODE)") (class "Default")
      (node (ref "C1_BAT1") (pin "1") (pinfunction "1_1") (pintype "passive"))
      (node (ref "D2") (pin "1") (pinfunction "CATHODE_1") (pintype "bidirectional"))
      (node (ref "IC4") (pin "1") (pinfunction "VIN_1") (pintype "bidirectional"))
      (node (ref "IC4") (pin "3") (pinfunction "CE_3") (pintype "bidirectional"))
      (node (ref "Q1") (pin "2") (pinfunction "S_2") (pintype "bidirectional"))
    )
    (net (code "23") (name "Net-(D3-A)") (class "Default")
      (node (ref "C4") (pin "1") (pinfunction "1_1") (pintype "passive"))
      (node (ref "D3") (pin "2") (pinfunction "A_2") (pintype "bidirectional"))
      (node (ref "D4") (pin "1") (pinfunction "K_1") (pintype "bidirectional"))
    )
    (net (code "24") (name "Net-(D7-CATHODE)") (class "Default")
      (node (ref "D7") (pin "1") (pinfunction "CATHODE_1") (pintype "bidirectional"))
      (node (ref "R_CAPACITOR") (pin "1") (pinfunction "1_1") (pintype "passive"))
    )
    (net (code "25") (name "Net-(EPD_C1-Pad1)") (class "Default")
      (node (ref "EPD_C1") (pin "1") (pinfunction "1_1") (pintype "passive"))
      (node (ref "J1") (pin "4") (pinfunction "4_4") (pintype "bidirectional"))
    )
    (net (code "26") (name "Net-(EPD_C2-Pad1)") (class "Default")
      (node (ref "EPD_C2") (pin "1") (pinfunction "1_1") (pintype "passive"))
      (node (ref "J1") (pin "5") (pinfunction "5_5") (pintype "bidirectional"))
    )
    (net (code "27") (name "Net-(EPD_C6-Pad1)") (class "Default")
      (node (ref "EPD_C6") (pin "1") (pinfunction "1_1") (pintype "passive"))
      (node (ref "J1") (pin "18") (pinfunction "18_18") (pintype "bidirectional"))
    )
    (net (code "28") (name "Net-(EPD_C7-Pad1)") (class "Default")
      (node (ref "EPD_C7") (pin "1") (pinfunction "1_1") (pintype "passive"))
      (node (ref "J1") (pin "19") (pinfunction "19_19") (pintype "bidirectional"))
    )
    (net (code "29") (name "Net-(EPD_C8-Pad1)") (class "Default")
      (node (ref "EPD_C8") (pin "1") (pinfunction "1_1") (pintype "passive"))
      (node (ref "J1") (pin "20") (pinfunction "20_20") (pintype "bidirectional"))
    )
    (net (code "30") (name "Net-(EPD_C10-Pad1)") (class "Default")
      (node (ref "EPD_C10") (pin "1") (pinfunction "1_1") (pintype "passive"))
      (node (ref "J1") (pin "22") (pinfunction "22_22") (pintype "bidirectional"))
    )
    (net (code "31") (name "Net-(EPD_C12-Pad1)") (class "Default")
      (node (ref "EPD_C12") (pin "1") (pinfunction "1_1") (pintype "passive"))
      (node (ref "J1") (pin "24") (pinfunction "24_24") (pintype "bidirectional"))
    )
    (net (code "32") (name "Net-(IC1-CT)") (class "Default")
      (node (ref "C_DELAY") (pin "1") (pinfunction "1_1") (pintype "passive"))
      (node (ref "IC1") (pin "5") (pinfunction "CT_5") (pintype "bidirectional"))
    )
    (net (code "33") (name "Net-(J2-PadA5)") (class "Default")
      (node (ref "J2") (pin "A5") (pinfunction "A5_A5") (pintype "bidirectional"))
      (node (ref "R2-USB1") (pin "2") (pinfunction "2_2") (pintype "passive"))
    )
    (net (code "34") (name "Net-(J2-PadB5)") (class "Default")
      (node (ref "J2") (pin "B5") (pinfunction "B5_B5") (pintype "bidirectional"))
      (node (ref "R2-USB") (pin "1") (pinfunction "1_1") (pintype "passive"))
    )
    (net (code "35") (name "Net-(MCP73831-PROG)") (class "Default")
      (node (ref "MCP73831") (pin "5") (pinfunction "PROG_5") (pintype "input"))
      (node (ref "R2_BAT") (pin "2") (pinfunction "2_2") (pintype "passive"))
    )
    (net (code "36") (name "Net-(MCP73831-STAT)") (class "Default")
      (node (ref "MCP73831") (pin "1") (pinfunction "STAT_1") (pintype "output"))
      (node (ref "R1_BAT") (pin "1") (pinfunction "1_1") (pintype "passive"))
    )
    (net (code "37") (name "PREVGH") (class "Default")
      (node (ref "D5") (pin "1") (pinfunction "K_1") (pintype "bidirectional"))
      (node (ref "EPD_C9") (pin "1") (pinfunction "1_1") (pintype "passive"))
      (node (ref "J1") (pin "21") (pinfunction "21_21") (pintype "bidirectional"))
    )
    (net (code "38") (name "PREVGL") (class "Default")
      (node (ref "D4") (pin "2") (pinfunction "A_2") (pintype "bidirectional"))
      (node (ref "EPD_C11") (pin "1") (pinfunction "1_1") (pintype "passive"))
      (node (ref "J1") (pin "23") (pinfunction "23_23") (pintype "bidirectional"))
    )
    (net (code "39") (name "RESE") (class "Default")
      (node (ref "J1") (pin "3") (pinfunction "3_3") (pintype "bidirectional"))
      (node (ref "Q3") (pin "2") (pinfunction "S_2") (pintype "bidirectional"))
      (node (ref "R3") (pin "1") (pinfunction "1_1") (pintype "passive"))
    )
    (net (code "40") (name "RESE'") (class "Default")
      (node (ref "R2") (pin "2") (pinfunction "2_2") (pintype "passive"))
      (node (ref "R3") (pin "2") (pinfunction "2_2") (pintype "passive"))
      (node (ref "SJ1") (pin "2") (pinfunction "2_2") (pintype "passive"))
    )
    (net (code "41") (name "RESET") (class "Default")
      (node (ref "C5") (pin "1") (pinfunction "1_1") (pintype "passive"))
      (node (ref "IC1") (pin "1") (pinfunction "VOUT_1") (pintype "bidirectional"))
      (node (ref "RESET_BUTTON") (pin "3") (pinfunction "3_3") (pintype "passive"))
      (node (ref "RESET_BUTTON") (pin "4") (pinfunction "4_4") (pintype "passive"))
      (node (ref "R_RESET") (pin "2") (pinfunction "2_2") (pintype "passive"))
      (node (ref "U2") (pin "3") (pinfunction "EN_3") (pintype "input"))
    )
    (net (code "42") (name "RTC_RST") (class "Default")
      (node (ref "U2") (pin "16") (pinfunction "IO18_16") (pintype "bidirectional"))
      (node (ref "U3") (pin "4") (pinfunction "~{RST}_4") (pintype "input"))
    )
    (net (code "43") (name "RX") (class "Default")
      (node (ref "TP2") (pin "TP") (pinfunction "TP_TP") (pintype "input"))
      (node (ref "U2") (pin "24") (pinfunction "RXD0/GPIO17_24") (pintype "bidirectional"))
    )
    (net (code "44") (name "SCK") (class "Default")
      (node (ref "D10") (pin "2") (pinfunction "2_2") (pintype "passive"))
      (node (ref "J1") (pin "13") (pinfunction "13_13") (pintype "bidirectional"))
      (node (ref "J4") (pin "P5") (pinfunction "CLK_P5") (pintype "bidirectional"))
      (node (ref "R6") (pin "1") (pinfunction "1_1") (pintype "passive"))
      (node (ref "TP8") (pin "TP") (pinfunction "TP_TP") (pintype "input"))
      (node (ref "U1") (pin "6") (pinfunction "CLK_6") (pintype "input"))
      (node (ref "U2") (pin "6") (pinfunction "IO6_6") (pintype "bidirectional"))
    )
    (net (code "45") (name "SCL") (class "Default")
      (node (ref "J3") (pin "4") (pinfunction "4_4") (pintype "passive"))
      (node (ref "R2_PINH") (pin "1") (pinfunction "1_1") (pintype "passive"))
      (node (ref "SENSOR2") (pin "4") (pinfunction "SCK_4") (pintype "input"))
      (node (ref "U2") (pin "20") (pinfunction "IO22_20") (pintype "bidirectional"))
      (node (ref "U3") (pin "16") (pinfunction "SCL_16") (pintype "input"))
      (node (ref "U4") (pin "7") (pinfunction "SCL_7") (pintype "input"))
    )
    (net (code "46") (name "SDA") (class "Default")
      (node (ref "J3") (pin "3") (pinfunction "3_3") (pintype "passive"))
      (node (ref "R1_PINH") (pin "1") (pinfunction "1_1") (pintype "passive"))
      (node (ref "SENSOR2") (pin "3") (pinfunction "SDI_3") (pintype "bidirectional"))
      (node (ref "U2") (pin "19") (pinfunction "IO21_19") (pintype "bidirectional"))
      (node (ref "U3") (pin "15") (pinfunction "SDA_15") (pintype "bidirectional"))
      (node (ref "U4") (pin "8") (pinfunction "SDA_8") (pintype "bidirectional"))
    )
    (net (code "47") (name "SRC") (class "Default")
      (node (ref "C4") (pin "2") (pinfunction "2_2") (pintype "passive"))
      (node (ref "D5") (pin "2") (pinfunction "A_2") (pintype "bidirectional"))
      (node (ref "L1") (pin "1") (pinfunction "1_1") (pintype "passive"))
      (node (ref "Q3") (pin "3") (pinfunction "D_3") (pintype "bidirectional"))
    )
    (net (code "48") (name "SS_SD") (class "Default")
      (node (ref "D8") (pin "2") (pinfunction "2_2") (pintype "passive"))
      (node (ref "J4") (pin "P2") (pinfunction "CD/DAT3_P2") (pintype "bidirectional"))
      (node (ref "R10") (pin "1") (pinfunction "1_1") (pintype "passive"))
      (node (ref "U2") (pin "4") (pinfunction "IO4_4") (pintype "bidirectional"))
    )
    (net (code "49") (name "TX") (class "Default")
      (node (ref "TP1") (pin "TP") (pinfunction "TP_TP") (pintype "input"))
      (node (ref "U2") (pin "25") (pinfunction "TXD0/GPIO16_25") (pintype "bidirectional"))
    )
    (net (code "50") (name "USB_D+") (class "Default")
      (node (ref "D1") (pin "1") (pinfunction "I/O1_1_1") (pintype "bidirectional"))
      (node (ref "U2") (pin "14") (pinfunction "IO13_14") (pintype "bidirectional"))
    )
    (net (code "51") (name "USB_D-") (class "Default")
      (node (ref "D1") (pin "3") (pinfunction "I/O2_1_3") (pintype "bidirectional"))
      (node (ref "U2") (pin "13") (pinfunction "IO12_13") (pintype "bidirectional"))
    )
    (net (code "52") (name "VBAT") (class "Default")
      (node (ref "C2_BAT") (pin "1") (pinfunction "1_1") (pintype "passive"))
      (node (ref "MCP73831") (pin "3") (pinfunction "VBAT_3") (pintype "power_in"))
      (node (ref "Q1") (pin "3") (pinfunction "D_3") (pintype "bidirectional"))
      (node (ref "TP3") (pin "TP") (pinfunction "TP_TP") (pintype "input"))
      (node (ref "U4") (pin "2") (pinfunction "CELL_2") (pintype "power_in"))
      (node (ref "U4") (pin "3") (pinfunction "VDD_3") (pintype "power_in"))
    )
    (net (code "53") (name "VBUS") (class "Default")
      (node (ref "C1_BAT") (pin "1") (pinfunction "1_1") (pintype "passive"))
      (node (ref "C4_USB") (pin "1") (pinfunction "1_1") (pintype "passive"))
      (node (ref "C5_USB") (pin "1") (pinfunction "1_1") (pintype "passive"))
      (node (ref "CHG_LED") (pin "A") (pinfunction "A_A") (pintype "passive"))
      (node (ref "D1") (pin "5") (pinfunction "VBUS_5") (pintype "bidirectional"))
      (node (ref "D2") (pin "2") (pinfunction "ANODE_2") (pintype "bidirectional"))
      (node (ref "MCP73831") (pin "4") (pinfunction "VIN_4") (pintype "power_in"))
      (node (ref "PFMF.050.1") (pin "2") (pinfunction "2_2") (pintype "passive"))
      (node (ref "Q1") (pin "1") (pinfunction "G_1") (pintype "bidirectional"))
      (node (ref "R1_PWRUSB") (pin "2") (pinfunction "2_2") (pintype "passive"))
      (node (ref "TP14") (pin "TP") (pinfunction "TP_TP") (pintype "input"))
    )
    (net (code "54") (name "VRTC") (class "Default")
      (node (ref "C10_SUPERCAP") (pin "2") (pinfunction "2_2") (pintype "passive"))
      (node (ref "C8") (pin "1") (pinfunction "1_1") (pintype "passive"))
      (node (ref "R_CAPACITOR") (pin "2") (pinfunction "2_2") (pintype "passive"))
      (node (ref "U3") (pin "14") (pinfunction "VBAT_14") (pintype "power_in"))
    )
    (net (code "55") (name "VUSB") (class "Default")
      (node (ref "J2") (pin "A4") (pinfunction "A4_A4") (pintype "bidirectional"))
      (node (ref "J2") (pin "A9") (pinfunction "A9_A9") (pintype "bidirectional"))
      (node (ref "J2") (pin "B4") (pinfunction "B4_B4") (pintype "bidirectional"))
      (node (ref "J2") (pin "B9") (pinfunction "B9_B9") (pintype "bidirectional"))
      (node (ref "PFMF.050.1") (pin "1") (pinfunction "1_1") (pintype "passive"))
    )
    (net (code "56") (name "unconnected-(IC1-NC-Pad4)") (class "Default")
      (node (ref "IC1") (pin "4") (pinfunction "NC_4") (pintype "no_connect"))
    )
    (net (code "57") (name "unconnected-(IC4-NC-Pad4)") (class "Default")
      (node (ref "IC4") (pin "4") (pinfunction "NC_4") (pintype "no_connect"))
    )
    (net (code "58") (name "unconnected-(J1-Pad1)") (class "Default")
      (node (ref "J1") (pin "1") (pinfunction "1_1") (pintype "bidirectional"))
    )
    (net (code "59") (name "unconnected-(J1-Pad6)") (class "Default")
      (node (ref "J1") (pin "6") (pinfunction "6_6") (pintype "bidirectional"))
    )
    (net (code "60") (name "unconnected-(J1-Pad7)") (class "Default")
      (node (ref "J1") (pin "7") (pinfunction "7_7") (pintype "bidirectional"))
    )
    (net (code "61") (name "unconnected-(J1-Pad8)") (class "Default")
      (node (ref "J1") (pin "8") (pinfunction "8_8") (pintype "bidirectional"))
    )
    (net (code "62") (name "unconnected-(J2-PadA8)") (class "Default")
      (node (ref "J2") (pin "A8") (pinfunction "A8_A8") (pintype "bidirectional"))
    )
    (net (code "63") (name "unconnected-(J2-PadB8)") (class "Default")
      (node (ref "J2") (pin "B8") (pinfunction "B8_B8") (pintype "bidirectional"))
    )
    (net (code "64") (name "unconnected-(J4-DAT1-PadP8)") (class "Default")
      (node (ref "J4") (pin "P8") (pinfunction "DAT1_P8") (pintype "bidirectional"))
    )
    (net (code "65") (name "unconnected-(J4-DAT2-PadP1)") (class "Default")
      (node (ref "J4") (pin "P1") (pinfunction "DAT2_P1") (pintype "bidirectional"))
    )
    (net (code "66") (name "unconnected-(J4-DETECTION_1-PadS1)") (class "Default")
      (node (ref "J4") (pin "S1") (pinfunction "DETECTION_1_S1") (pintype "bidirectional"))
    )
    (net (code "67") (name "unconnected-(J4-DETECTION_2-PadS2)") (class "Default")
      (node (ref "J4") (pin "S2") (pinfunction "DETECTION_2_S2") (pintype "bidirectional"))
    )
    (net (code "68") (name "unconnected-(U2-NC-Pad22)") (class "Default")
      (node (ref "U2") (pin "22") (pinfunction "NC_22") (pintype "no_connect"))
    )
    (net (code "69") (name "unconnected-(U4-~{ALERT}-Pad5)") (class "Default")
      (node (ref "U4") (pin "5") (pinfunction "~{ALERT}_5") (pintype "output"))
    )
  )
)
